# FTDI.net
KiCad netlist of a schematic drawn in Altium Designer
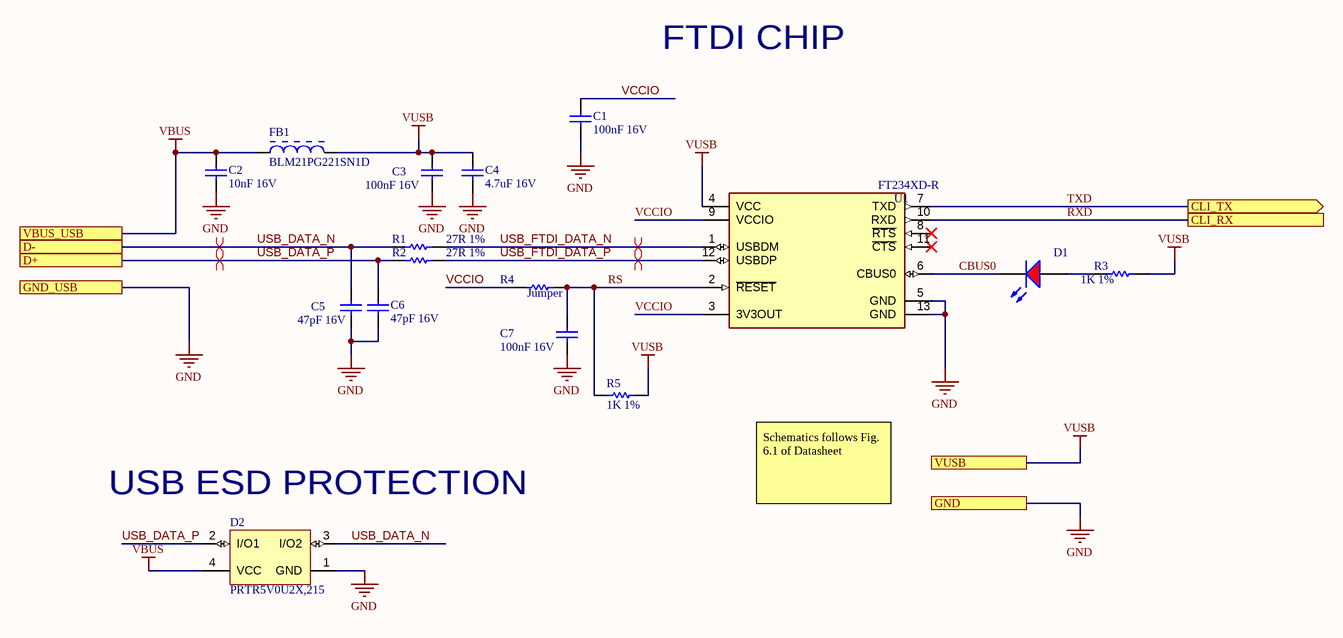
[diagram p0: FTDI.SchDoc]

(export (version "E")
  (design (tool "Eeschema 10.0.6"))
  (components
    (comp (ref "C1")
      (value "100nF 16V")
      (footprint "CAPC0603(1608)100_N")
      (description "CAP 100nF 16V ±10% 0603 (1608 Metric) Thickness 1mm SMD")
      (fields (field (name "TOLERANCE") "Â±10%"))
      (libsource (lib "Altium Content Vault") (part "CAP"))
    )
    (comp (ref "C2")
      (value "10nF 16V")
      (footprint "CAPC0603(1608)100_N")
      (description "CAP 10nF 16V ±10% 0603 (1608 Metric) Thickness 1mm SMD")
      (fields (field (name "TOLERANCE") "Â±10%"))
      (libsource (lib "Altium Content Vault") (part "CAP"))
    )
    (comp (ref "C3")
      (value "100nF 16V")
      (footprint "CAPC0603(1608)100_N")
      (description "CAP 100nF 16V ±10% 0603 (1608 Metric) Thickness 1mm SMD")
      (fields (field (name "TOLERANCE") "Â±10%"))
      (libsource (lib "Altium Content Vault") (part "CAP"))
    )
    (comp (ref "C4")
      (value "4.7uF 16V")
      (footprint "CAPC0805(2012)145_N")
      (description "CAP 4.7uF 16V -20% to +80% 0805 (2012 Metric) Thickness 1.45mm SMD")
      (fields (field (name "TOLERANCE") "-20% to +80%"))
      (libsource (lib "Altium Content Vault") (part "CAP"))
    )
    (comp (ref "C5")
      (value "47pF 16V")
      (footprint "CAPC0603(1608)100_N")
      (description "CAP 47pF 16V ±0.5pF 0603 (1608 Metric) Thickness 1mm SMD")
      (fields (field (name "TOLERANCE") "Â±0.5pF"))
      (libsource (lib "Altium Content Vault") (part "CAP"))
    )
    (comp (ref "C6")
      (value "47pF 16V")
      (footprint "CAPC0603(1608)100_N")
      (description "CAP 47pF 16V ±0.5pF 0603 (1608 Metric) Thickness 1mm SMD")
      (fields (field (name "TOLERANCE") "Â±0.5pF"))
      (libsource (lib "Altium Content Vault") (part "CAP"))
    )
    (comp (ref "C7")
      (value "100nF 16V")
      (footprint "CAPC0603(1608)100_N")
      (description "CAP 100nF 16V ±10% 0603 (1608 Metric) Thickness 1mm SMD")
      (fields (field (name "TOLERANCE") "Â±10%"))
      (libsource (lib "Altium Content Vault") (part "CAP"))
    )
    (comp (ref "D1")
      (value "LTST-C170CKT")
      (footprint "LTST-C170CKT_V")
      (description "LED Uni-Color Red, 100 mW, 200 mA, -55 to 85 degC, 2-Pin SMD, RoHS, Tape and Reel")
      (fields (field (name "MANUFACTURER") "Lite-On"))
      (libsource (lib "Altium Content Vault") (part "LED-RED-AK-2"))
    )
    (comp (ref "D2")
      (value "PRTR5V0U2X,215")
      (footprint "NXP-SOT143B-4_V")
      (fields (field (name "MANUFACTURER") "NXP Semiconductors"))
      (libsource (lib "Altium Content Vault") (part "NXP-PRTR5V0U2X,215-4"))
    )
    (comp (ref "FB1")
      (value "BLM21PG221SN1D")
      (footprint "MURA-BLM21-B20-CHIP-2_V2")
      (fields (field (name "MANUFACTURER") "Murata"))
      (libsource (lib "Altium Content Vault") (part "MURA-FB-2"))
    )
    (comp (ref "R1")
      (value "27R 1%")
      (footprint "RESC0603(1608)_N")
      (description "27R 0.1W 1% 0603 (1608 Metric)  SMD")
      (fields (field (name "TOLERANCE") "1 %") (field (name "POWER") "0.1 W"))
      (libsource (lib "Altium Content Vault") (part "RES"))
    )
    (comp (ref "R2")
      (value "27R 1%")
      (footprint "RESC0603(1608)_N")
      (description "27R 0.1W 1% 0603 (1608 Metric)  SMD")
      (fields (field (name "TOLERANCE") "1 %") (field (name "POWER") "0.1 W"))
      (libsource (lib "Altium Content Vault") (part "RES"))
    )
    (comp (ref "R3")
      (value "1K 1%")
      (footprint "RESC0603(1608)_N")
      (description "1K 0.1W 1% 0603 (1608 Metric)  SMD")
      (fields (field (name "TOLERANCE") "1 %") (field (name "POWER") "0.1 W"))
      (libsource (lib "Altium Content Vault") (part "RES"))
    )
    (comp (ref "R4")
      (value "Jumper")
      (footprint "RESC0603(1608)_N")
      (description "Jumper 0603 (1608 Metric)")
      (fields (field (name "POWER") "None"))
      (libsource (lib "Altium Content Vault") (part "RES"))
    )
    (comp (ref "R5")
      (value "1K 1%")
      (footprint "RESC0603(1608)_N")
      (description "1K 0.1W 1% 0603 (1608 Metric)  SMD")
      (fields (field (name "TOLERANCE") "1 %") (field (name "POWER") "0.1 W"))
      (libsource (lib "Altium Content Vault") (part "RES"))
    )
    (comp (ref "U1")
      (value "FT234XD-R")
      (footprint "FP-DFN-12-IPC_B")
      (description "IC USB SERIAL BASIC UART 12DFN")
      (libsource (lib "Altium Content Vault") (part "4bef3367ed9f9051bcb84ab46edda1c"))
    )
  )
  (nets
    (net (code "1") (name "/CBUS0") (class "Default")
      (node (ref "D1") (pin "2") (pinfunction "K_2") (pintype "passive"))
      (node (ref "U1") (pin "6") (pinfunction "CBUS0_6") (pintype "bidirectional"))
    )
    (net (code "2") (name "/RS") (class "Default")
      (node (ref "C7") (pin "2") (pinfunction "2_2") (pintype "passive"))
      (node (ref "R4") (pin "2") (pinfunction "2_2") (pintype "passive"))
      (node (ref "R5") (pin "2") (pinfunction "2_2") (pintype "passive"))
      (node (ref "U1") (pin "2") (pinfunction "~{RESET}_2") (pintype "input"))
    )
    (net (code "3") (name "/RXD") (class "Default")
      (node (ref "U1") (pin "10") (pinfunction "RXD_10") (pintype "output"))
    )
    (net (code "4") (name "/TXD") (class "Default")
      (node (ref "U1") (pin "7") (pinfunction "TXD_7") (pintype "output"))
    )
    (net (code "5") (name "/USB_DATA_N") (class "Default")
      (node (ref "C5") (pin "2") (pinfunction "2_2") (pintype "passive"))
      (node (ref "D2") (pin "3") (pinfunction "I/O2_3") (pintype "bidirectional"))
      (node (ref "R1") (pin "1") (pinfunction "1_1") (pintype "passive"))
    )
    (net (code "6") (name "/USB_DATA_P") (class "Default")
      (node (ref "C6") (pin "2") (pinfunction "2_2") (pintype "passive"))
      (node (ref "D2") (pin "2") (pinfunction "I/O1_2") (pintype "bidirectional"))
      (node (ref "R2") (pin "1") (pinfunction "1_1") (pintype "passive"))
    )
    (net (code "7") (name "/USB_FTDI_DATA_N") (class "Default")
      (node (ref "R1") (pin "2") (pinfunction "2_2") (pintype "passive"))
      (node (ref "U1") (pin "1") (pinfunction "USBDM_1") (pintype "bidirectional"))
    )
    (net (code "8") (name "/USB_FTDI_DATA_P") (class "Default")
      (node (ref "R2") (pin "2") (pinfunction "2_2") (pintype "passive"))
      (node (ref "U1") (pin "12") (pinfunction "USBDP_12") (pintype "bidirectional"))
    )
    (net (code "9") (name "/VCCIO") (class "Default")
      (node (ref "C1") (pin "2") (pinfunction "2_2") (pintype "passive"))
      (node (ref "R4") (pin "1") (pinfunction "1_1") (pintype "passive"))
      (node (ref "U1") (pin "3") (pinfunction "3V3OUT_3") (pintype "power_in"))
      (node (ref "U1") (pin "9") (pinfunction "VCCIO_9") (pintype "power_in"))
    )
    (net (code "10") (name "GND") (class "Default")
      (node (ref "C1") (pin "1") (pinfunction "1_1") (pintype "passive"))
      (node (ref "C2") (pin "1") (pinfunction "1_1") (pintype "passive"))
      (node (ref "C3") (pin "1") (pinfunction "1_1") (pintype "passive"))
      (node (ref "C4") (pin "1") (pinfunction "1_1") (pintype "passive"))
      (node (ref "C5") (pin "1") (pinfunction "1_1") (pintype "passive"))
      (node (ref "C6") (pin "1") (pinfunction "1_1") (pintype "passive"))
      (node (ref "C7") (pin "1") (pinfunction "1_1") (pintype "passive"))
      (node (ref "D2") (pin "1") (pinfunction "GND_1") (pintype "power_in"))
      (node (ref "U1") (pin "13") (pinfunction "GND_13") (pintype "power_in"))
      (node (ref "U1") (pin "5") (pinfunction "GND_5") (pintype "power_in"))
    )
    (net (code "11") (name "Net-(D1-A)") (class "Default")
      (node (ref "D1") (pin "1") (pinfunction "A_1") (pintype "passive"))
      (node (ref "R3") (pin "1") (pinfunction "1_1") (pintype "passive"))
    )
    (net (code "12") (name "VBUS") (class "Default")
      (node (ref "C2") (pin "2") (pinfunction "2_2") (pintype "passive"))
      (node (ref "D2") (pin "4") (pinfunction "VCC_4") (pintype "power_in"))
      (node (ref "FB1") (pin "1") (pinfunction "1_1") (pintype "passive"))
    )
    (net (code "13") (name "VUSB") (class "Default")
      (node (ref "C3") (pin "2") (pinfunction "2_2") (pintype "passive"))
      (node (ref "C4") (pin "2") (pinfunction "2_2") (pintype "passive"))
      (node (ref "FB1") (pin "2") (pinfunction "2_2") (pintype "passive"))
      (node (ref "R3") (pin "2") (pinfunction "2_2") (pintype "passive"))
      (node (ref "R5") (pin "1") (pinfunction "1_1") (pintype "passive"))
      (node (ref "U1") (pin "4") (pinfunction "VCC_4") (pintype "power_in"))
    )
    (net (code "14") (name "unconnected-(U1-~{CTS}-Pad11)") (class "Default")
      (node (ref "U1") (pin "11") (pinfunction "~{CTS}_11") (pintype "input+no_connect"))
    )
    (net (code "15") (name "unconnected-(U1-~{RTS}-Pad8)") (class "Default")
      (node (ref "U1") (pin "8") (pinfunction "~{RTS}_8") (pintype "input+no_connect"))
    )
  )
)
